# hb41.net
KiCad netlist of a schematic drawn in EAGLE
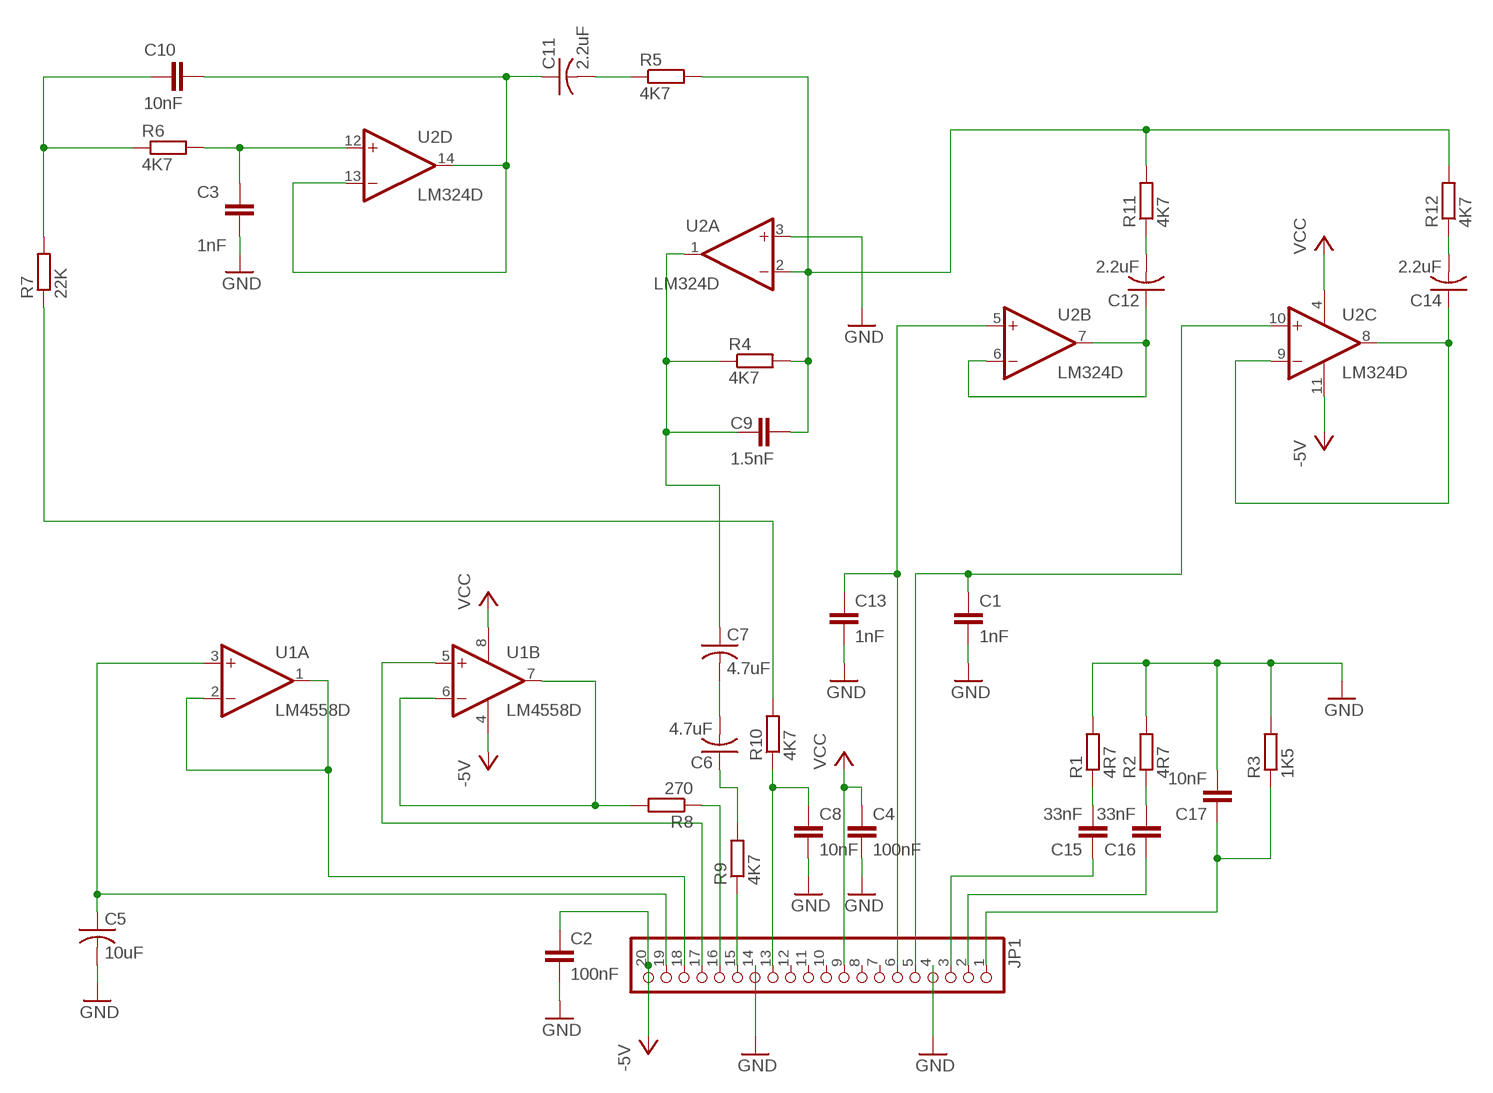
[diagram p0: schematic, sheet 1]

(export (version "E")
  (design (tool "Eeschema 10.0.6"))
  (components
    (comp (ref "C1")
      (value "1nF")
      (footprint "eagle-import:C0805K")
      (libsource (lib "eagle-import") (part "C-EUC0805K"))
    )
    (comp (ref "C2")
      (value "100nF")
      (footprint "eagle-import:C0805K")
      (libsource (lib "eagle-import") (part "C-EUC0805K"))
    )
    (comp (ref "C3")
      (value "1nF")
      (footprint "eagle-import:C0603")
      (libsource (lib "eagle-import") (part "C-EUC0603"))
    )
    (comp (ref "C4")
      (value "100nF")
      (footprint "eagle-import:C0603")
      (libsource (lib "eagle-import") (part "C-EUC0603"))
    )
    (comp (ref "C5")
      (value "10uF")
      (footprint "eagle-import:C1206K")
      (libsource (lib "eagle-import") (part "C-USC1206K"))
    )
    (comp (ref "C6")
      (value "4.7uF")
      (footprint "eagle-import:C1206K")
      (libsource (lib "eagle-import") (part "C-USC1206K"))
    )
    (comp (ref "C7")
      (value "4.7uF")
      (footprint "eagle-import:C1206K")
      (libsource (lib "eagle-import") (part "C-USC1206K"))
    )
    (comp (ref "C8")
      (value "10nF")
      (footprint "eagle-import:C0603")
      (libsource (lib "eagle-import") (part "C-EUC0603"))
    )
    (comp (ref "C9")
      (value "1.5nF")
      (footprint "eagle-import:C0805K")
      (libsource (lib "eagle-import") (part "C-EUC0805K"))
    )
    (comp (ref "C10")
      (value "10nF")
      (footprint "eagle-import:C0805K")
      (libsource (lib "eagle-import") (part "C-EUC0805K"))
    )
    (comp (ref "C11")
      (value "2.2uF")
      (footprint "eagle-import:C1206K")
      (libsource (lib "eagle-import") (part "C-USC1206K"))
    )
    (comp (ref "C12")
      (value "2.2uF")
      (footprint "eagle-import:C1206K")
      (libsource (lib "eagle-import") (part "C-USC1206K"))
    )
    (comp (ref "C13")
      (value "1nF")
      (footprint "eagle-import:C0805K")
      (libsource (lib "eagle-import") (part "C-EUC0805K"))
    )
    (comp (ref "C14")
      (value "2.2uF")
      (footprint "eagle-import:C1206K")
      (libsource (lib "eagle-import") (part "C-USC1206K"))
    )
    (comp (ref "C15")
      (value "33nF")
      (footprint "eagle-import:C0603")
      (libsource (lib "eagle-import") (part "C-EUC0603"))
    )
    (comp (ref "C16")
      (value "33nF")
      (footprint "eagle-import:C0603")
      (libsource (lib "eagle-import") (part "C-EUC0603"))
    )
    (comp (ref "C17")
      (value "10nF")
      (footprint "eagle-import:C0603")
      (libsource (lib "eagle-import") (part "C-EUC0603"))
    )
    (comp (ref "JP1")
      (value "PINHD-1X20-BIG")
      (footprint "eagle-import:1X20-BIG")
      (libsource (lib "eagle-import") (part "PINHD-1X20-BIG"))
    )
    (comp (ref "R1")
      (value "4R7")
      (footprint "eagle-import:R0603")
      (libsource (lib "eagle-import") (part "R-EU_R0603"))
    )
    (comp (ref "R2")
      (value "4R7")
      (footprint "eagle-import:R0603")
      (libsource (lib "eagle-import") (part "R-EU_R0603"))
    )
    (comp (ref "R3")
      (value "1K5")
      (footprint "eagle-import:R0603")
      (libsource (lib "eagle-import") (part "R-EU_R0603"))
    )
    (comp (ref "R4")
      (value "4K7")
      (footprint "eagle-import:R0603")
      (libsource (lib "eagle-import") (part "R-EU_R0603"))
    )
    (comp (ref "R5")
      (value "4K7")
      (footprint "eagle-import:R0603")
      (libsource (lib "eagle-import") (part "R-EU_R0603"))
    )
    (comp (ref "R6")
      (value "4K7")
      (footprint "eagle-import:R0603")
      (libsource (lib "eagle-import") (part "R-EU_R0603"))
    )
    (comp (ref "R7")
      (value "22K")
      (footprint "eagle-import:R0603")
      (libsource (lib "eagle-import") (part "R-EU_R0603"))
    )
    (comp (ref "R8")
      (value "270")
      (footprint "eagle-import:R0603")
      (libsource (lib "eagle-import") (part "R-EU_R0603"))
    )
    (comp (ref "R9")
      (value "4K7")
      (footprint "eagle-import:R0603")
      (libsource (lib "eagle-import") (part "R-EU_R0603"))
    )
    (comp (ref "R10")
      (value "4K7")
      (footprint "eagle-import:R0603")
      (libsource (lib "eagle-import") (part "R-EU_R0603"))
    )
    (comp (ref "R11")
      (value "4K7")
      (footprint "eagle-import:R0603")
      (libsource (lib "eagle-import") (part "R-EU_R0603"))
    )
    (comp (ref "R12")
      (value "4K7")
      (footprint "eagle-import:R0603")
      (libsource (lib "eagle-import") (part "R-EU_R0603"))
    )
    (comp (ref "U1")
      (value "LM4558D")
      (footprint "eagle-import:SO08")
      (libsource (lib "eagle-import") (part "4558DLM"))
    )
    (comp (ref "U2")
      (value "LM324D")
      (footprint "eagle-import:SO14")
      (libsource (lib "eagle-import") (part "LM324D"))
    )
  )
  (nets
    (net (code "1") (name "-5V") (class "Default")
      (node (ref "C2") (pin "1") (pinfunction "1_1") (pintype "passive"))
      (node (ref "JP1") (pin "20") (pinfunction "20_20") (pintype "passive"))
      (node (ref "U1") (pin "4") (pinfunction "V-_4") (pintype "power_in"))
      (node (ref "U2") (pin "11") (pinfunction "V-_11") (pintype "power_in"))
    )
    (net (code "2") (name "GND") (class "Default")
      (node (ref "C1") (pin "2") (pinfunction "2_2") (pintype "passive"))
      (node (ref "C13") (pin "2") (pinfunction "2_2") (pintype "passive"))
      (node (ref "C17") (pin "2") (pinfunction "2_2") (pintype "passive"))
      (node (ref "C2") (pin "2") (pinfunction "2_2") (pintype "passive"))
      (node (ref "C3") (pin "1") (pinfunction "1_1") (pintype "passive"))
      (node (ref "C4") (pin "2") (pinfunction "2_2") (pintype "passive"))
      (node (ref "C5") (pin "2") (pinfunction "2_2") (pintype "passive"))
      (node (ref "C8") (pin "2") (pinfunction "2_2") (pintype "passive"))
      (node (ref "JP1") (pin "14") (pinfunction "14_14") (pintype "passive"))
      (node (ref "JP1") (pin "4") (pinfunction "4_4") (pintype "passive"))
      (node (ref "R1") (pin "2") (pinfunction "2_2") (pintype "passive"))
      (node (ref "R2") (pin "2") (pinfunction "2_2") (pintype "passive"))
      (node (ref "R3") (pin "2") (pinfunction "2_2") (pintype "passive"))
      (node (ref "U2") (pin "3") (pinfunction "+IN_3") (pintype "input"))
    )
    (net (code "3") (name "Net-(C6-Pad1)") (class "Default")
      (node (ref "C6") (pin "1") (pinfunction "1_1") (pintype "passive"))
      (node (ref "R9") (pin "2") (pinfunction "2_2") (pintype "passive"))
    )
    (net (code "4") (name "Net-(C6-Pad2)") (class "Default")
      (node (ref "C6") (pin "2") (pinfunction "2_2") (pintype "passive"))
      (node (ref "C7") (pin "2") (pinfunction "2_2") (pintype "passive"))
    )
    (net (code "5") (name "Net-(C8-Pad1)") (class "Default")
      (node (ref "C8") (pin "1") (pinfunction "1_1") (pintype "passive"))
      (node (ref "JP1") (pin "13") (pinfunction "13_13") (pintype "passive"))
      (node (ref "R10") (pin "1") (pinfunction "1_1") (pintype "passive"))
    )
    (net (code "6") (name "Net-(C10-Pad1)") (class "Default")
      (node (ref "C10") (pin "1") (pinfunction "1_1") (pintype "passive"))
      (node (ref "R6") (pin "1") (pinfunction "1_1") (pintype "passive"))
      (node (ref "R7") (pin "2") (pinfunction "2_2") (pintype "passive"))
    )
    (net (code "7") (name "Net-(C11-Pad2)") (class "Default")
      (node (ref "C11") (pin "2") (pinfunction "2_2") (pintype "passive"))
      (node (ref "R5") (pin "1") (pinfunction "1_1") (pintype "passive"))
    )
    (net (code "8") (name "Net-(C12-Pad2)") (class "Default")
      (node (ref "C12") (pin "2") (pinfunction "2_2") (pintype "passive"))
      (node (ref "R11") (pin "1") (pinfunction "1_1") (pintype "passive"))
    )
    (net (code "9") (name "Net-(C14-Pad2)") (class "Default")
      (node (ref "C14") (pin "2") (pinfunction "2_2") (pintype "passive"))
      (node (ref "R12") (pin "1") (pinfunction "1_1") (pintype "passive"))
    )
    (net (code "10") (name "Net-(C15-Pad1)") (class "Default")
      (node (ref "C15") (pin "1") (pinfunction "1_1") (pintype "passive"))
      (node (ref "JP1") (pin "3") (pinfunction "3_3") (pintype "passive"))
    )
    (net (code "11") (name "Net-(C15-Pad2)") (class "Default")
      (node (ref "C15") (pin "2") (pinfunction "2_2") (pintype "passive"))
      (node (ref "R1") (pin "1") (pinfunction "1_1") (pintype "passive"))
    )
    (net (code "12") (name "Net-(C16-Pad1)") (class "Default")
      (node (ref "C16") (pin "1") (pinfunction "1_1") (pintype "passive"))
      (node (ref "JP1") (pin "2") (pinfunction "2_2") (pintype "passive"))
    )
    (net (code "13") (name "Net-(C16-Pad2)") (class "Default")
      (node (ref "C16") (pin "2") (pinfunction "2_2") (pintype "passive"))
      (node (ref "R2") (pin "1") (pinfunction "1_1") (pintype "passive"))
    )
    (net (code "14") (name "Net-(C17-Pad1)") (class "Default")
      (node (ref "C17") (pin "1") (pinfunction "1_1") (pintype "passive"))
      (node (ref "JP1") (pin "1") (pinfunction "1_1") (pintype "passive"))
      (node (ref "R3") (pin "1") (pinfunction "1_1") (pintype "passive"))
    )
    (net (code "15") (name "Net-(JP1-Pad15)") (class "Default")
      (node (ref "JP1") (pin "15") (pinfunction "15_15") (pintype "passive"))
      (node (ref "R9") (pin "1") (pinfunction "1_1") (pintype "passive"))
    )
    (net (code "16") (name "Net-(JP1-Pad16)") (class "Default")
      (node (ref "JP1") (pin "16") (pinfunction "16_16") (pintype "passive"))
      (node (ref "R8") (pin "1") (pinfunction "1_1") (pintype "passive"))
    )
    (net (code "17") (name "Net-(R10-Pad2)") (class "Default")
      (node (ref "R10") (pin "2") (pinfunction "2_2") (pintype "passive"))
      (node (ref "R7") (pin "1") (pinfunction "1_1") (pintype "passive"))
    )
    (net (code "18") (name "Net-(U1A-+IN)") (class "Default")
      (node (ref "C5") (pin "1") (pinfunction "1_1") (pintype "passive"))
      (node (ref "JP1") (pin "19") (pinfunction "19_19") (pintype "passive"))
      (node (ref "U1") (pin "3") (pinfunction "+IN_3") (pintype "input"))
    )
    (net (code "19") (name "Net-(U1A--IN)") (class "Default")
      (node (ref "JP1") (pin "18") (pinfunction "18_18") (pintype "passive"))
      (node (ref "U1") (pin "1") (pinfunction "OUT_1") (pintype "output"))
      (node (ref "U1") (pin "2") (pinfunction "-IN_2") (pintype "input"))
    )
    (net (code "20") (name "Net-(U1B-+IN)") (class "Default")
      (node (ref "JP1") (pin "17") (pinfunction "17_17") (pintype "passive"))
      (node (ref "U1") (pin "5") (pinfunction "+IN_5") (pintype "input"))
    )
    (net (code "21") (name "Net-(U1B--IN)") (class "Default")
      (node (ref "R8") (pin "2") (pinfunction "2_2") (pintype "passive"))
      (node (ref "U1") (pin "6") (pinfunction "-IN_6") (pintype "input"))
      (node (ref "U1") (pin "7") (pinfunction "OUT_7") (pintype "output"))
    )
    (net (code "22") (name "Net-(U2A--IN)") (class "Default")
      (node (ref "C9") (pin "2") (pinfunction "2_2") (pintype "passive"))
      (node (ref "R11") (pin "2") (pinfunction "2_2") (pintype "passive"))
      (node (ref "R12") (pin "2") (pinfunction "2_2") (pintype "passive"))
      (node (ref "R4") (pin "2") (pinfunction "2_2") (pintype "passive"))
      (node (ref "R5") (pin "2") (pinfunction "2_2") (pintype "passive"))
      (node (ref "U2") (pin "2") (pinfunction "-IN_2") (pintype "input"))
    )
    (net (code "23") (name "Net-(U2A-OUT)") (class "Default")
      (node (ref "C7") (pin "1") (pinfunction "1_1") (pintype "passive"))
      (node (ref "C9") (pin "1") (pinfunction "1_1") (pintype "passive"))
      (node (ref "R4") (pin "1") (pinfunction "1_1") (pintype "passive"))
      (node (ref "U2") (pin "1") (pinfunction "OUT_1") (pintype "output"))
    )
    (net (code "24") (name "Net-(U2B-+IN)") (class "Default")
      (node (ref "C13") (pin "1") (pinfunction "1_1") (pintype "passive"))
      (node (ref "JP1") (pin "6") (pinfunction "6_6") (pintype "passive"))
      (node (ref "U2") (pin "5") (pinfunction "+IN_5") (pintype "input"))
    )
    (net (code "25") (name "Net-(U2B--IN)") (class "Default")
      (node (ref "C12") (pin "1") (pinfunction "1_1") (pintype "passive"))
      (node (ref "U2") (pin "6") (pinfunction "-IN_6") (pintype "input"))
      (node (ref "U2") (pin "7") (pinfunction "OUT_7") (pintype "output"))
    )
    (net (code "26") (name "Net-(U2C-+IN)") (class "Default")
      (node (ref "C1") (pin "1") (pinfunction "1_1") (pintype "passive"))
      (node (ref "JP1") (pin "5") (pinfunction "5_5") (pintype "passive"))
      (node (ref "U2") (pin "10") (pinfunction "+IN_10") (pintype "input"))
    )
    (net (code "27") (name "Net-(U2C--IN)") (class "Default")
      (node (ref "C14") (pin "1") (pinfunction "1_1") (pintype "passive"))
      (node (ref "U2") (pin "8") (pinfunction "OUT_8") (pintype "output"))
      (node (ref "U2") (pin "9") (pinfunction "-IN_9") (pintype "input"))
    )
    (net (code "28") (name "Net-(U2D-+IN)") (class "Default")
      (node (ref "C3") (pin "2") (pinfunction "2_2") (pintype "passive"))
      (node (ref "R6") (pin "2") (pinfunction "2_2") (pintype "passive"))
      (node (ref "U2") (pin "12") (pinfunction "+IN_12") (pintype "input"))
    )
    (net (code "29") (name "Net-(U2D--IN)") (class "Default")
      (node (ref "C10") (pin "2") (pinfunction "2_2") (pintype "passive"))
      (node (ref "C11") (pin "1") (pinfunction "1_1") (pintype "passive"))
      (node (ref "U2") (pin "13") (pinfunction "-IN_13") (pintype "input"))
      (node (ref "U2") (pin "14") (pinfunction "OUT_14") (pintype "output"))
    )
    (net (code "30") (name "VCC") (class "Default")
      (node (ref "C4") (pin "1") (pinfunction "1_1") (pintype "passive"))
      (node (ref "JP1") (pin "9") (pinfunction "9_9") (pintype "passive"))
      (node (ref "U1") (pin "8") (pinfunction "V+_8") (pintype "power_in"))
      (node (ref "U2") (pin "4") (pinfunction "V+_4") (pintype "power_in"))
    )
    (net (code "31") (name "unconnected-(JP1-Pad7)") (class "Default")
      (node (ref "JP1") (pin "7") (pinfunction "7_7") (pintype "passive"))
    )
    (net (code "32") (name "unconnected-(JP1-Pad8)") (class "Default")
      (node (ref "JP1") (pin "8") (pinfunction "8_8") (pintype "passive"))
    )
    (net (code "33") (name "unconnected-(JP1-Pad10)") (class "Default")
      (node (ref "JP1") (pin "10") (pinfunction "10_10") (pintype "passive"))
    )
    (net (code "34") (name "unconnected-(JP1-Pad11)") (class "Default")
      (node (ref "JP1") (pin "11") (pinfunction "11_11") (pintype "passive"))
    )
    (net (code "35") (name "unconnected-(JP1-Pad12)") (class "Default")
      (node (ref "JP1") (pin "12") (pinfunction "12_12") (pintype "passive"))
    )
  )
)
